# ADG_919.net
KiCad netlist of a schematic drawn in EAGLE
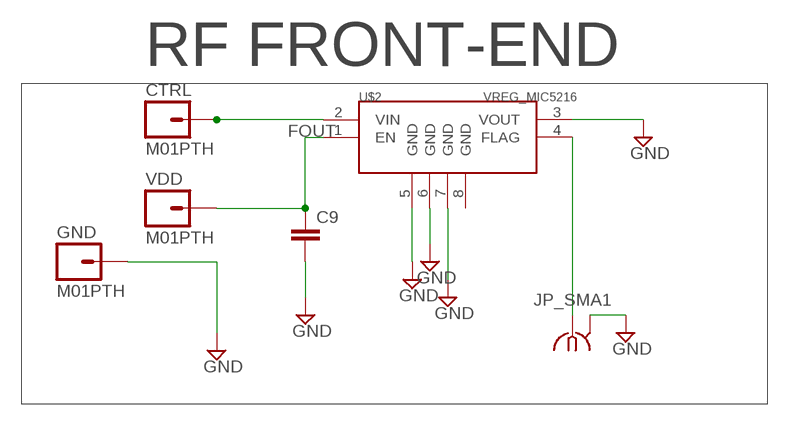
[diagram p0: schematic, sheet 1]

(export (version "E")
  (design (tool "Eeschema 10.0.6"))
  (components
    (comp (ref "C9")
      (value "CAP0603-CAP")
      (footprint "eagle-import:0603-CAP")
      (libsource (lib "eagle-import") (part "CAP0603-CAP"))
    )
    (comp (ref "CTRL")
      (value "M01PTH")
      (footprint "eagle-import:1X01")
      (libsource (lib "eagle-import") (part "M01PTH"))
    )
    (comp (ref "GND")
      (value "M01PTH")
      (footprint "eagle-import:1X01")
      (libsource (lib "eagle-import") (part "M01PTH"))
    )
    (comp (ref "JP_SMA1")
      (value "SMA-142-0701-881/886")
      (footprint "eagle-import:J502-ND-142-0701-881_886")
      (fields (field (name "MF") "JOHNSON COMPONENTS") (field (name "MPN") "142-0701-881"))
      (libsource (lib "eagle-import") (part "SMA-142-0701-881/886"))
    )
    (comp (ref "U$2")
      (value "VREG_MIC5216")
      (footprint "eagle-import:MSOP8")
      (libsource (lib "eagle-import") (part "VREG_MIC5216"))
    )
    (comp (ref "VDD")
      (value "M01PTH")
      (footprint "eagle-import:1X01")
      (libsource (lib "eagle-import") (part "M01PTH"))
    )
  )
  (nets
    (net (code "1") (name "/FOUT") (class "Default")
      (node (ref "CTRL") (pin "1") (pinfunction "1_1") (pintype "passive"))
      (node (ref "U$2") (pin "2") (pinfunction "VIN_2") (pintype "bidirectional"))
    )
    (net (code "2") (name "GND") (class "Default")
      (node (ref "C9") (pin "2") (pinfunction "2_2") (pintype "passive"))
      (node (ref "GND") (pin "1") (pinfunction "1_1") (pintype "passive"))
      (node (ref "JP_SMA1") (pin "G@1") (pinfunction "2_G@1") (pintype "passive"))
      (node (ref "JP_SMA1") (pin "G@2") (pinfunction "2_G@2") (pintype "passive"))
      (node (ref "JP_SMA1") (pin "G@3") (pinfunction "2_G@3") (pintype "passive"))
      (node (ref "JP_SMA1") (pin "G@4") (pinfunction "2_G@4") (pintype "passive"))
      (node (ref "U$2") (pin "3") (pinfunction "VOUT_3") (pintype "bidirectional"))
      (node (ref "U$2") (pin "5") (pinfunction "GND_5") (pintype "bidirectional"))
      (node (ref "U$2") (pin "6") (pinfunction "GND_6") (pintype "bidirectional"))
      (node (ref "U$2") (pin "7") (pinfunction "GND_7") (pintype "bidirectional"))
    )
    (net (code "3") (name "Net-(U$2-EN)") (class "Default")
      (node (ref "C9") (pin "1") (pinfunction "1_1") (pintype "passive"))
      (node (ref "U$2") (pin "1") (pinfunction "EN_1") (pintype "bidirectional"))
      (node (ref "VDD") (pin "1") (pinfunction "1_1") (pintype "passive"))
    )
    (net (code "4") (name "Net-(U$2-FLAG)") (class "Default")
      (node (ref "JP_SMA1") (pin "1") (pinfunction "1_1") (pintype "passive"))
      (node (ref "U$2") (pin "4") (pinfunction "FLAG_4") (pintype "bidirectional"))
    )
    (net (code "5") (name "unconnected-(U$2-GND-Pad8)") (class "Default")
      (node (ref "U$2") (pin "8") (pinfunction "GND_8") (pintype "bidirectional"))
    )
  )
)
